# Main.net
KiCad netlist of a schematic drawn in Altium Designer
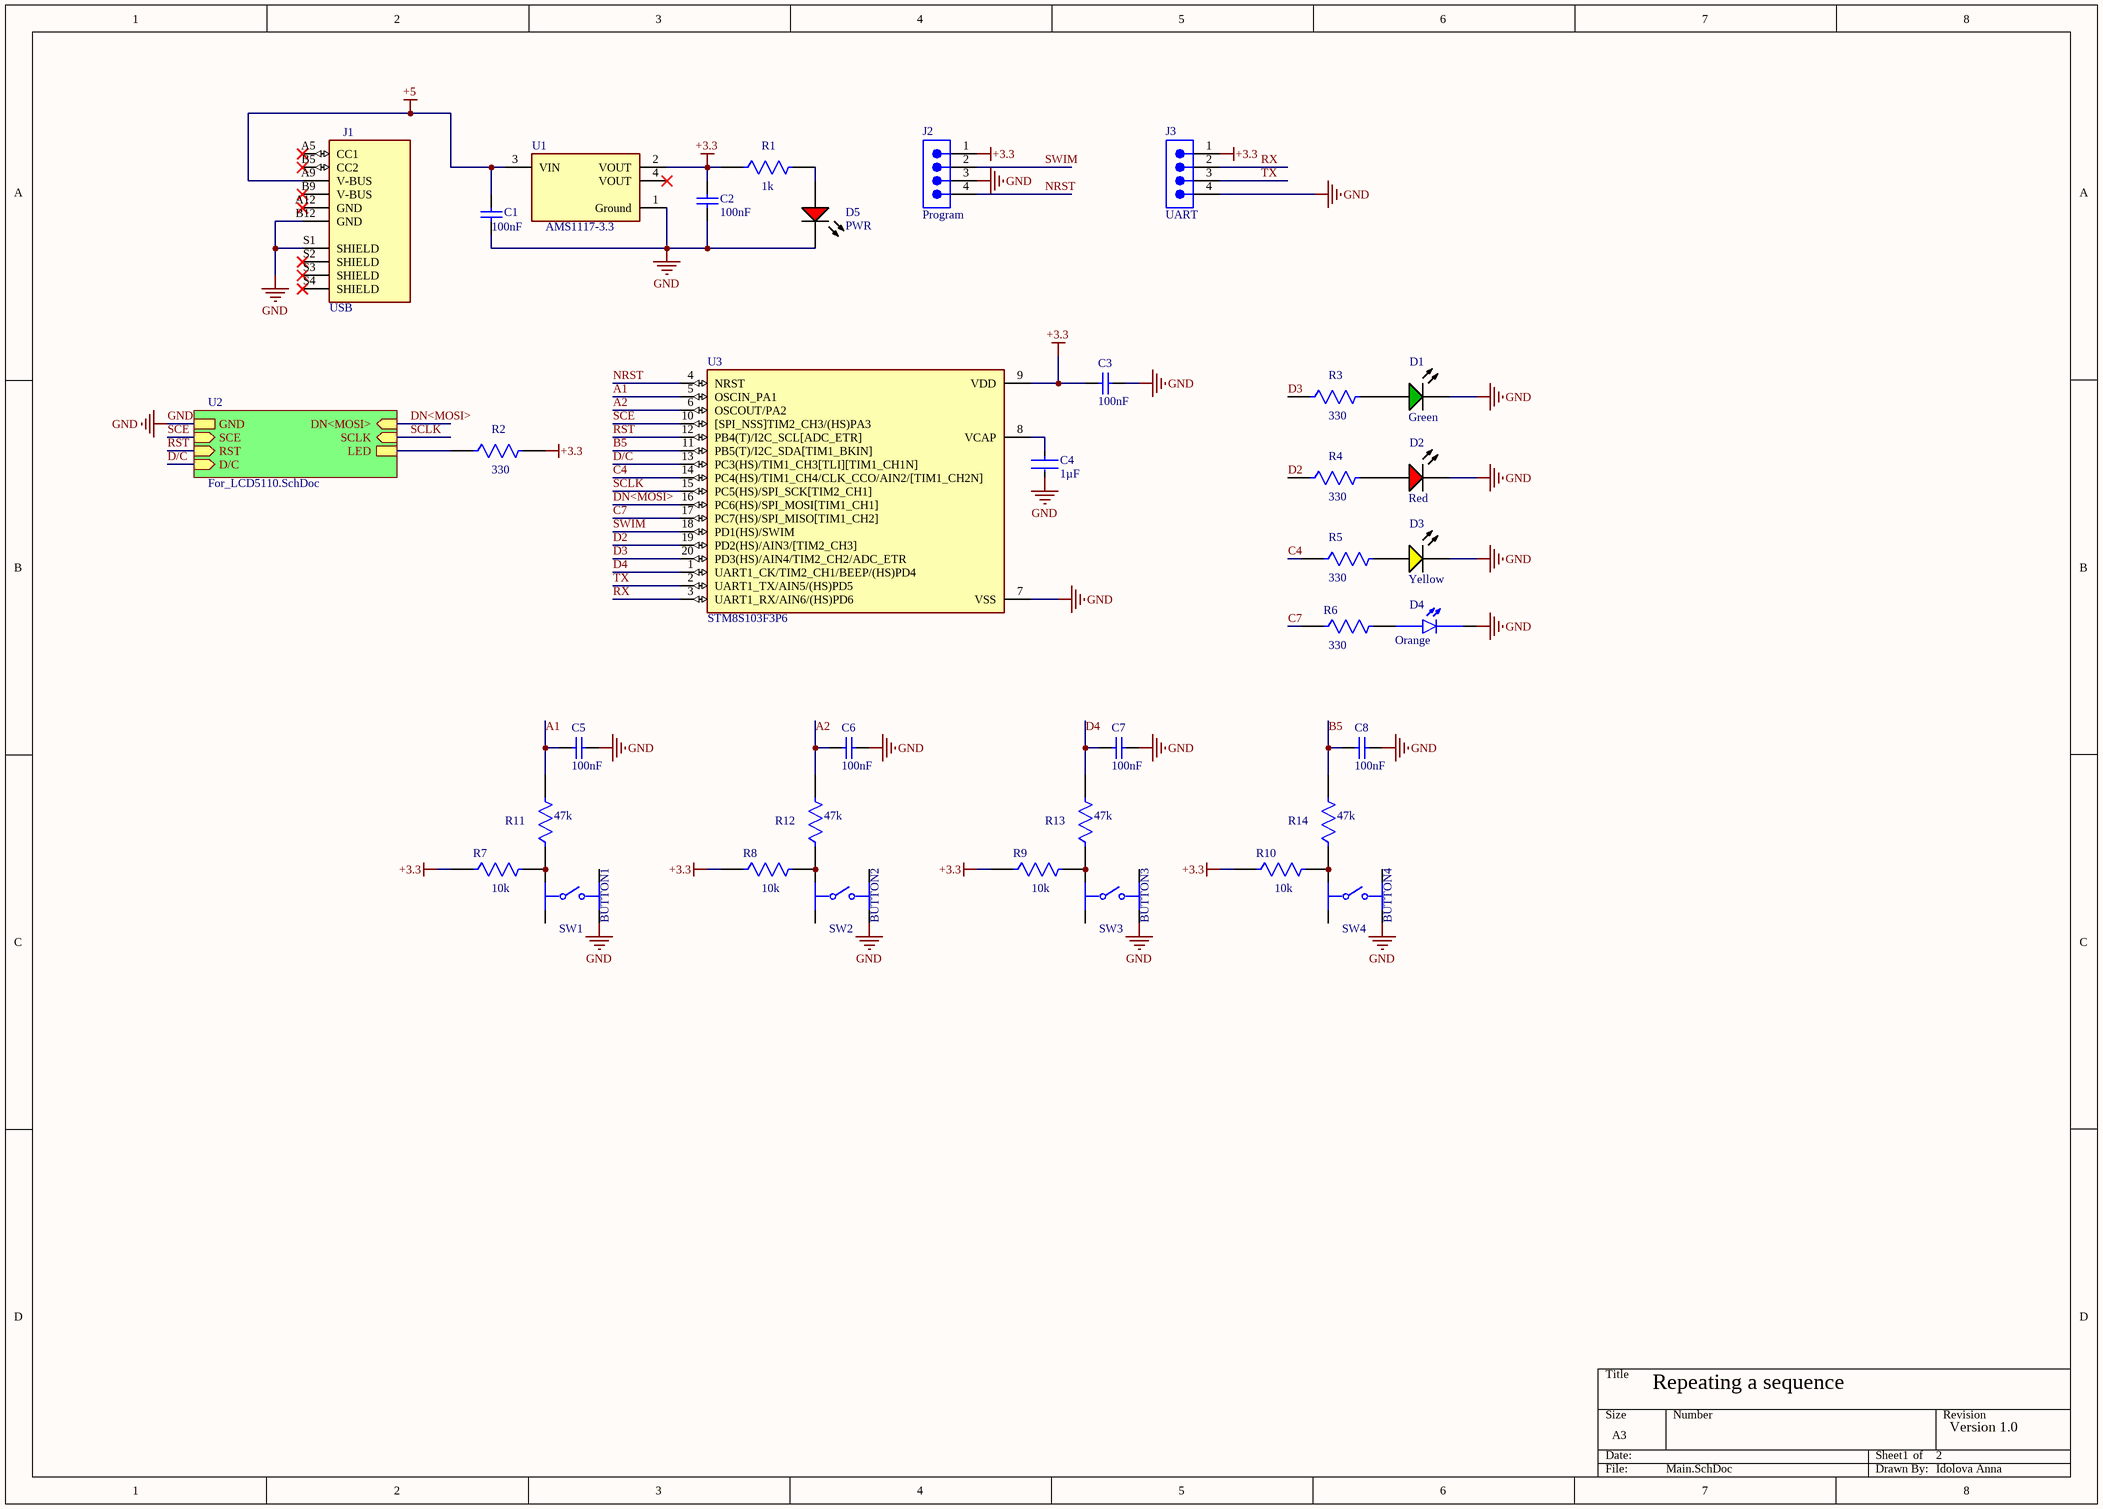
[diagram p0: Main.SchDoc]

(export (version "E")
  (design (tool "Eeschema 10.0.6"))
  (components
    (comp (ref "C1")
      (value "100nF")
      (footprint "CAPC1206(3216)100_N")
      (fields (field (name "Comment") "CAPACITOR_1206ZC104JAT2A"))
      (libsource (lib "National Technical University of Ukraine Igor Sikorsky Kyiv Polytechnic Institute- Educator Program") (part "CAP"))
    )
    (comp (ref "C2")
      (value "100nF")
      (footprint "CAPC1206(3216)100_N")
      (fields (field (name "Comment") "CAPACITOR_1206ZC104JAT2A"))
      (libsource (lib "National Technical University of Ukraine Igor Sikorsky Kyiv Polytechnic Institute- Educator Program") (part "CAP"))
    )
    (comp (ref "C3")
      (value "100nF")
      (footprint "CAPC1206(3216)100_N")
      (fields (field (name "Comment") "CAPACITOR_1206ZC104JAT2A"))
      (libsource (lib "National Technical University of Ukraine Igor Sikorsky Kyiv Polytechnic Institute- Educator Program") (part "CAP"))
    )
    (comp (ref "C4")
      (value "1µF")
      (footprint "FP-CL21-IPC_B")
      (fields (field (name "Comment") "CL21F105ZAFNNNF"))
      (libsource (lib "National Technical University of Ukraine Igor Sikorsky Kyiv Polytechnic Institute- Educator Program") (part "b4654b650e69147ec39a6b967a45e02"))
    )
    (comp (ref "C5")
      (value "100nF")
      (footprint "CAPC1206(3216)100_N")
      (fields (field (name "Comment") "CAPACITOR_1206ZC104JAT2A"))
      (libsource (lib "National Technical University of Ukraine Igor Sikorsky Kyiv Polytechnic Institute- Educator Program") (part "CAP"))
    )
    (comp (ref "C6")
      (value "100nF")
      (footprint "CAPC1206(3216)100_N")
      (fields (field (name "Comment") "CAPACITOR_1206ZC104JAT2A"))
      (libsource (lib "National Technical University of Ukraine Igor Sikorsky Kyiv Polytechnic Institute- Educator Program") (part "CAP"))
    )
    (comp (ref "C7")
      (value "100nF")
      (footprint "CAPC1206(3216)100_N")
      (fields (field (name "Comment") "CAPACITOR_1206ZC104JAT2A"))
      (libsource (lib "National Technical University of Ukraine Igor Sikorsky Kyiv Polytechnic Institute- Educator Program") (part "CAP"))
    )
    (comp (ref "C8")
      (value "100nF")
      (footprint "CAPC1206(3216)100_N")
      (fields (field (name "Comment") "CAPACITOR_1206ZC104JAT2A"))
      (libsource (lib "National Technical University of Ukraine Igor Sikorsky Kyiv Polytechnic Institute- Educator Program") (part "CAP"))
    )
    (comp (ref "D1")
      (value "Green")
      (footprint "KING-WP7113SGD_V")
      (description "LED Green, 62.5 mW, 25 mA, -40 to 85 degC, 2-Pin THD, RoHS, Bulk")
      (fields (field (name "MANUFACTURER") "Kingbright") (field (name "POWER") "62.5mW"))
      (libsource (lib "National Technical University of Ukraine Igor Sikorsky Kyiv Polytechnic Institute- Educator Program") (part "LED-GREEN-AK-2"))
    )
    (comp (ref "D2")
      (value "Red")
      (footprint "KING-WP7113SRDD_V")
      (description "The Super Bright Red Source Color Device, 1.85 V, -40 to 85 degC, 2-Pin THD, RoHS, Tape and Reel")
      (fields (field (name "MANUFACTURER") "Kingbright"))
      (libsource (lib "National Technical University of Ukraine Igor Sikorsky Kyiv Polytechnic Institute- Educator Program") (part "LED-RED-AK-2"))
    )
    (comp (ref "D3")
      (value "Yellow")
      (footprint "KING-WP7113SYD_V")
      (description "The Super Bright Yellow Source Color Device, 2 V, -40 to 85 degC, 2-Pin THD, RoHS, Tape and Reel")
      (fields (field (name "MANUFACTURER") "Kingbright"))
      (libsource (lib "National Technical University of Ukraine Igor Sikorsky Kyiv Polytechnic Institute- Educator Program") (part "LED-YELLOW-AK-2"))
    )
    (comp (ref "D4")
      (value "Orange")
      (footprint "LED_WP7113SEC")
      (description "LED Thru-Hole Orange T1-3/4 5mm Clear Lens 30mA 610nm 2500mcd Round")
      (fields (field (name "MP") "WP7113SEC") (field (name "MF") "Kingbright"))
      (libsource (lib "National Technical University of Ukraine Igor Sikorsky Kyiv Polytechnic Institute- Educator Program") (part "WP7113SEC"))
    )
    (comp (ref "D5")
      (value "PWR")
      (footprint "KING-WP7113SRDD_V")
      (description "The Super Bright Red Source Color Device, 1.85 V, -40 to 85 degC, 2-Pin THD, RoHS, Tape and Reel")
      (fields (field (name "MANUFACTURER") "Kingbright"))
      (libsource (lib "National Technical University of Ukraine Igor Sikorsky Kyiv Polytechnic Institute- Educator Program") (part "LED-RED-AK-2"))
    )
    (comp (ref "J1")
      (value "USB")
      (footprint "CUI_UJC-HP-3-SMT-TR")
      (fields (field (name "MP") "UJC-HP-3-SMT-TR"))
      (libsource (lib "National Technical University of Ukraine Igor Sikorsky Kyiv Polytechnic Institute- Educator Program") (part "UJC-HP-3-SMT-TR"))
    )
    (comp (ref "J2")
      (value "Program")
      (footprint "61300411021")
      (libsource (lib "National Technical University of Ukraine Igor Sikorsky Kyiv Polytechnic Institute- Educator Program") (part "CMP-1502-01063-3"))
    )
    (comp (ref "J3")
      (value "UART")
      (footprint "61300411021")
      (libsource (lib "National Technical University of Ukraine Igor Sikorsky Kyiv Polytechnic Institute- Educator Program") (part "CMP-1502-01063-3"))
    )
    (comp (ref "R1")
      (value "1k")
      (footprint "FP-RC1005-IPC_C")
      (fields
        (field (name "POWER") "60mW")
        (field (name "TOLERANCE") "1%")
        (field (name "Comment") "RESISTOR__RC1005F102CS")
      )
      (libsource (lib "National Technical University of Ukraine Igor Sikorsky Kyiv Polytechnic Institute- Educator Program") (part "1029c3af85768c4190bb7ad29bc67b5"))
    )
    (comp (ref "R2")
      (value "330")
      (footprint "FP-MCR18-IPC_B")
      (fields
        (field (name "TOLERANCE") "1%")
        (field (name "POWER") "250mW")
        (field (name "Comment") "MCR18EZPF3300")
      )
      (libsource (lib "National Technical University of Ukraine Igor Sikorsky Kyiv Polytechnic Institute- Educator Program") (part "1029c3af85768c4190bb7ad29bc67b5"))
    )
    (comp (ref "R3")
      (value "330")
      (footprint "FP-MCR18-IPC_B")
      (fields
        (field (name "TOLERANCE") "1%")
        (field (name "POWER") "250mW")
        (field (name "Comment") "MCR18EZPF3300")
      )
      (libsource (lib "National Technical University of Ukraine Igor Sikorsky Kyiv Polytechnic Institute- Educator Program") (part "1029c3af85768c4190bb7ad29bc67b5"))
    )
    (comp (ref "R4")
      (value "330")
      (footprint "FP-MCR18-IPC_B")
      (fields
        (field (name "TOLERANCE") "1%")
        (field (name "POWER") "250mW")
        (field (name "Comment") "MCR18EZPF3300")
      )
      (libsource (lib "National Technical University of Ukraine Igor Sikorsky Kyiv Polytechnic Institute- Educator Program") (part "1029c3af85768c4190bb7ad29bc67b5"))
    )
    (comp (ref "R5")
      (value "330")
      (footprint "FP-MCR18-IPC_B")
      (fields
        (field (name "TOLERANCE") "1%")
        (field (name "POWER") "250mW")
        (field (name "Comment") "MCR18EZPF3300")
      )
      (libsource (lib "National Technical University of Ukraine Igor Sikorsky Kyiv Polytechnic Institute- Educator Program") (part "1029c3af85768c4190bb7ad29bc67b5"))
    )
    (comp (ref "R6")
      (value "330")
      (footprint "FP-MCR18-IPC_B")
      (fields
        (field (name "TOLERANCE") "1%")
        (field (name "POWER") "250mW")
        (field (name "Comment") "MCR18EZPF3300")
      )
      (libsource (lib "National Technical University of Ukraine Igor Sikorsky Kyiv Polytechnic Institute- Educator Program") (part "1029c3af85768c4190bb7ad29bc67b5"))
    )
    (comp (ref "R7")
      (value "10k")
      (footprint "FP-TFCR0402-IPC_A")
      (description "Fixed Resistor, Thin Film, 0.063W, 10000ohm, 25V, 0.1% +/-Tol, 50ppm/Cel, Surface Mount, 0402")
      (fields (field (name "TOLERANCE") "0.1%") (field (name "Comment") "TFCR0402-16W-C-1002BT"))
      (libsource (lib "National Technical University of Ukraine Igor Sikorsky Kyiv Polytechnic Institute- Educator Program") (part "1029c3af85768c4190bb7ad29bc67b5"))
    )
    (comp (ref "R8")
      (value "10k")
      (footprint "FP-TFCR0402-IPC_A")
      (description "Fixed Resistor, Thin Film, 0.063W, 10000ohm, 25V, 0.1% +/-Tol, 50ppm/Cel, Surface Mount, 0402")
      (fields (field (name "TOLERANCE") "0.1%") (field (name "Comment") "TFCR0402-16W-C-1002BT"))
      (libsource (lib "National Technical University of Ukraine Igor Sikorsky Kyiv Polytechnic Institute- Educator Program") (part "1029c3af85768c4190bb7ad29bc67b5"))
    )
    (comp (ref "R9")
      (value "10k")
      (footprint "FP-TFCR0402-IPC_A")
      (description "Fixed Resistor, Thin Film, 0.063W, 10000ohm, 25V, 0.1% +/-Tol, 50ppm/Cel, Surface Mount, 0402")
      (fields (field (name "TOLERANCE") "0.1%") (field (name "Comment") "TFCR0402-16W-C-1002BT"))
      (libsource (lib "National Technical University of Ukraine Igor Sikorsky Kyiv Polytechnic Institute- Educator Program") (part "1029c3af85768c4190bb7ad29bc67b5"))
    )
    (comp (ref "R10")
      (value "10k")
      (footprint "FP-TFCR0402-IPC_A")
      (description "Fixed Resistor, Thin Film, 0.063W, 10000ohm, 25V, 0.1% +/-Tol, 50ppm/Cel, Surface Mount, 0402")
      (fields (field (name "TOLERANCE") "0.1%") (field (name "Comment") "TFCR0402-16W-C-1002BT"))
      (libsource (lib "National Technical University of Ukraine Igor Sikorsky Kyiv Polytechnic Institute- Educator Program") (part "1029c3af85768c4190bb7ad29bc67b5"))
    )
    (comp (ref "R11")
      (value "47k")
      (footprint "FP-RC1005-IPC_C")
      (description "Res Thin Film 0603 47K Ohm 0.1% 0.063W(1/16W) ±25ppm/C Pad SMD T/R Medical")
      (fields (field (name "TOLERANCE") "0.1%") (field (name "Comment") "RESISTOR__RC1005F102CS"))
      (libsource (lib "") (part "1029c3af85768c4190bb7ad29bc67b5_1"))
    )
    (comp (ref "R12")
      (value "47k")
      (footprint "FP-RC1005-IPC_C")
      (description "Res Thin Film 0603 47K Ohm 0.1% 0.063W(1/16W) ±25ppm/C Pad SMD T/R Medical")
      (fields (field (name "TOLERANCE") "0.1%") (field (name "Comment") "RESISTOR__RC1005F102CS"))
      (libsource (lib "") (part "1029c3af85768c4190bb7ad29bc67b5_1"))
    )
    (comp (ref "R13")
      (value "47k")
      (footprint "FP-RC1005-IPC_C")
      (description "Res Thin Film 0603 47K Ohm 0.1% 0.063W(1/16W) ±25ppm/C Pad SMD T/R Medical")
      (fields (field (name "TOLERANCE") "0.1%") (field (name "Comment") "RESISTOR__RC1005F102CS"))
      (libsource (lib "") (part "1029c3af85768c4190bb7ad29bc67b5_1"))
    )
    (comp (ref "R14")
      (value "47k")
      (footprint "FP-RC1005-IPC_C")
      (description "Res Thin Film 0603 47K Ohm 0.1% 0.063W(1/16W) ±25ppm/C Pad SMD T/R Medical")
      (fields (field (name "TOLERANCE") "0.1%") (field (name "Comment") "RESISTOR__RC1005F102CS"))
      (libsource (lib "") (part "1029c3af85768c4190bb7ad29bc67b5_1"))
    )
    (comp (ref "SW1")
      (value "BUTTON1")
      (footprint "FP-PTS645SM43SMTR92LFS-MFG")
      (libsource (lib "National Technical University of Ukraine Igor Sikorsky Kyiv Polytechnic Institute- Educator Program") (part "1adf0dd01260c80cf25a44bfd6b99ba"))
    )
    (comp (ref "SW2")
      (value "BUTTON2")
      (footprint "FP-PTS645SM43SMTR92LFS-MFG")
      (libsource (lib "National Technical University of Ukraine Igor Sikorsky Kyiv Polytechnic Institute- Educator Program") (part "1adf0dd01260c80cf25a44bfd6b99ba"))
    )
    (comp (ref "SW3")
      (value "BUTTON3")
      (footprint "FP-PTS645SM43SMTR92LFS-MFG")
      (libsource (lib "National Technical University of Ukraine Igor Sikorsky Kyiv Polytechnic Institute- Educator Program") (part "1adf0dd01260c80cf25a44bfd6b99ba"))
    )
    (comp (ref "SW4")
      (value "BUTTON4")
      (footprint "FP-PTS645SM43SMTR92LFS-MFG")
      (libsource (lib "National Technical University of Ukraine Igor Sikorsky Kyiv Polytechnic Institute- Educator Program") (part "1adf0dd01260c80cf25a44bfd6b99ba"))
    )
    (comp (ref "U1")
      (value "AMS1117-3.3")
      (footprint "FP-AMS1117-IPC_B")
      (description "Fixed Positive LDO Regulator, 3.3V, 1.3V Dropout, PDSO3")
      (libsource (lib "National Technical University of Ukraine Igor Sikorsky Kyiv Polytechnic Institute- Educator Program") (part "8bdbb5f8e77002000e30dd2845d0354"))
    )
    (comp (ref "U3")
      (value "STM8S103F3P6")
      (footprint "SOP65P640X120-20N")
      (description "STM8 series Microcontroller IC 8-Bit 16MHz 8KB (8K x 8) FLASH 20-TSSOP")
      (fields (field (name "MF") "STMicroelectronics"))
      (libsource (lib "National Technical University of Ukraine Igor Sikorsky Kyiv Polytechnic Institute- Educator Program") (part "STM8S103F3P6"))
    )
  )
  (nets
    (net (code "1") (name "+3.3") (class "Default")
      (node (ref "C2") (pin "2") (pinfunction "2_2") (pintype "passive"))
      (node (ref "C3") (pin "1") (pinfunction "1_1") (pintype "passive"))
      (node (ref "J2") (pin "1") (pinfunction "1_1") (pintype "passive"))
      (node (ref "J3") (pin "1") (pinfunction "1_1") (pintype "passive"))
      (node (ref "R1") (pin "1") (pinfunction "1_1") (pintype "passive"))
      (node (ref "R10") (pin "1") (pinfunction "1_1") (pintype "passive"))
      (node (ref "R2") (pin "2") (pinfunction "2_2") (pintype "passive"))
      (node (ref "R7") (pin "1") (pinfunction "1_1") (pintype "passive"))
      (node (ref "R8") (pin "1") (pinfunction "1_1") (pintype "passive"))
      (node (ref "R9") (pin "1") (pinfunction "1_1") (pintype "passive"))
      (node (ref "U1") (pin "2") (pinfunction "VOUT_2") (pintype "passive"))
      (node (ref "U3") (pin "9") (pinfunction "VDD_9") (pintype "power_in"))
    )
    (net (code "2") (name "+5") (class "Default")
      (node (ref "C1") (pin "2") (pinfunction "2_2") (pintype "passive"))
      (node (ref "J1") (pin "A9") (pinfunction "V-BUS_A9") (pintype "power_in"))
      (node (ref "U1") (pin "3") (pinfunction "VIN_3") (pintype "power_in"))
    )
    (net (code "3") (name "/A1") (class "Default")
      (node (ref "C5") (pin "1") (pinfunction "1_1") (pintype "passive"))
      (node (ref "R11") (pin "1") (pinfunction "1_1") (pintype "passive"))
      (node (ref "U3") (pin "5") (pinfunction "OSCIN_PA1_5") (pintype "bidirectional"))
    )
    (net (code "4") (name "/A2") (class "Default")
      (node (ref "C6") (pin "1") (pinfunction "1_1") (pintype "passive"))
      (node (ref "R12") (pin "1") (pinfunction "1_1") (pintype "passive"))
      (node (ref "U3") (pin "6") (pinfunction "OSCOUT/PA2_6") (pintype "bidirectional"))
    )
    (net (code "5") (name "/B5") (class "Default")
      (node (ref "C8") (pin "1") (pinfunction "1_1") (pintype "passive"))
      (node (ref "R14") (pin "1") (pinfunction "1_1") (pintype "passive"))
      (node (ref "U3") (pin "11") (pinfunction "PB5(T)/I2C_SDA[TIM1_BKIN]_11") (pintype "bidirectional"))
    )
    (net (code "6") (name "/C4") (class "Default")
      (node (ref "R5") (pin "1") (pinfunction "1_1") (pintype "passive"))
      (node (ref "U3") (pin "14") (pinfunction "PC4(HS)/TIM1_CH4/CLK_CCO/AIN2/[TIM1_CH2N]_14") (pintype "bidirectional"))
    )
    (net (code "7") (name "/C7") (class "Default")
      (node (ref "R6") (pin "1") (pinfunction "1_1") (pintype "passive"))
      (node (ref "U3") (pin "17") (pinfunction "PC7(HS)/SPI_MISO[TIM1_CH2]_17") (pintype "bidirectional"))
    )
    (net (code "8") (name "/D2") (class "Default")
      (node (ref "R4") (pin "1") (pinfunction "1_1") (pintype "passive"))
      (node (ref "U3") (pin "19") (pinfunction "PD2(HS)/AIN3/[TIM2_CH3]_19") (pintype "bidirectional"))
    )
    (net (code "9") (name "/D3") (class "Default")
      (node (ref "R3") (pin "1") (pinfunction "1_1") (pintype "passive"))
      (node (ref "U3") (pin "20") (pinfunction "PD3(HS)/AIN4/TIM2_CH2/ADC_ETR_20") (pintype "bidirectional"))
    )
    (net (code "10") (name "/D4") (class "Default")
      (node (ref "C7") (pin "1") (pinfunction "1_1") (pintype "passive"))
      (node (ref "R13") (pin "1") (pinfunction "1_1") (pintype "passive"))
      (node (ref "U3") (pin "1") (pinfunction "UART1_CK/TIM2_CH1/BEEP/(HS)PD4_1") (pintype "bidirectional"))
    )
    (net (code "11") (name "/DN<MOSI>") (class "Default")
      (node (ref "U3") (pin "16") (pinfunction "PC6(HS)/SPI_MOSI[TIM1_CH1]_16") (pintype "bidirectional"))
    )
    (net (code "12") (name "/D{slash}C") (class "Default")
      (node (ref "U3") (pin "13") (pinfunction "PC3(HS)/TIM1_CH3[TLI][TIM1_CH1N]_13") (pintype "bidirectional"))
    )
    (net (code "13") (name "/LED") (class "Default")
      (node (ref "R2") (pin "1") (pinfunction "1_1") (pintype "passive"))
    )
    (net (code "14") (name "/NRST") (class "Default")
      (node (ref "J2") (pin "4") (pinfunction "4_4") (pintype "passive"))
      (node (ref "U3") (pin "4") (pinfunction "NRST_4") (pintype "bidirectional"))
    )
    (net (code "15") (name "/RST") (class "Default")
      (node (ref "U3") (pin "12") (pinfunction "PB4(T)/I2C_SCL[ADC_ETR]_12") (pintype "bidirectional"))
    )
    (net (code "16") (name "/RX") (class "Default")
      (node (ref "J3") (pin "2") (pinfunction "2_2") (pintype "passive"))
      (node (ref "U3") (pin "3") (pinfunction "UART1_RX/AIN6/(HS)PD6_3") (pintype "bidirectional"))
    )
    (net (code "17") (name "/SCE") (class "Default")
      (node (ref "U3") (pin "10") (pinfunction "[SPI_NSS]TIM2_CH3/(HS)PA3_10") (pintype "bidirectional"))
    )
    (net (code "18") (name "/SCLK") (class "Default")
      (node (ref "U3") (pin "15") (pinfunction "PC5(HS)/SPI_SCK[TIM2_CH1]_15") (pintype "bidirectional"))
    )
    (net (code "19") (name "/SWIM") (class "Default")
      (node (ref "J2") (pin "2") (pinfunction "2_2") (pintype "passive"))
      (node (ref "U3") (pin "18") (pinfunction "PD1(HS)/SWIM_18") (pintype "bidirectional"))
    )
    (net (code "20") (name "/TX") (class "Default")
      (node (ref "J3") (pin "3") (pinfunction "3_3") (pintype "passive"))
      (node (ref "U3") (pin "2") (pinfunction "UART1_TX/AIN5/(HS)PD5_2") (pintype "bidirectional"))
    )
    (net (code "21") (name "GND") (class "Default")
      (node (ref "C1") (pin "1") (pinfunction "1_1") (pintype "passive"))
      (node (ref "C2") (pin "1") (pinfunction "1_1") (pintype "passive"))
      (node (ref "C3") (pin "2") (pinfunction "2_2") (pintype "passive"))
      (node (ref "C4") (pin "2") (pinfunction "2_2") (pintype "passive"))
      (node (ref "C5") (pin "2") (pinfunction "2_2") (pintype "passive"))
      (node (ref "C6") (pin "2") (pinfunction "2_2") (pintype "passive"))
      (node (ref "C7") (pin "2") (pinfunction "2_2") (pintype "passive"))
      (node (ref "C8") (pin "2") (pinfunction "2_2") (pintype "passive"))
      (node (ref "D1") (pin "2") (pinfunction "K_2") (pintype "passive"))
      (node (ref "D2") (pin "2") (pinfunction "K_2") (pintype "passive"))
      (node (ref "D3") (pin "2") (pinfunction "K_2") (pintype "passive"))
      (node (ref "D4") (pin "C") (pinfunction "C_C") (pintype "passive"))
      (node (ref "D5") (pin "2") (pinfunction "K_2") (pintype "passive"))
      (node (ref "J1") (pin "B12") (pinfunction "GND_B12") (pintype "power_in"))
      (node (ref "J1") (pin "S1") (pinfunction "SHIELD_S1") (pintype "passive"))
      (node (ref "J2") (pin "3") (pinfunction "3_3") (pintype "passive"))
      (node (ref "J3") (pin "4") (pinfunction "4_4") (pintype "passive"))
      (node (ref "SW1") (pin "2") (pinfunction "2_2") (pintype "passive"))
      (node (ref "SW2") (pin "2") (pinfunction "2_2") (pintype "passive"))
      (node (ref "SW3") (pin "2") (pinfunction "2_2") (pintype "passive"))
      (node (ref "SW4") (pin "2") (pinfunction "2_2") (pintype "passive"))
      (node (ref "U1") (pin "1") (pinfunction "Ground_1") (pintype "power_in"))
      (node (ref "U3") (pin "7") (pinfunction "VSS_7") (pintype "power_in"))
    )
    (net (code "22") (name "Net-(D1-A)") (class "Default")
      (node (ref "D1") (pin "1") (pinfunction "A_1") (pintype "passive"))
      (node (ref "R3") (pin "2") (pinfunction "2_2") (pintype "passive"))
    )
    (net (code "23") (name "Net-(D2-A)") (class "Default")
      (node (ref "D2") (pin "1") (pinfunction "A_1") (pintype "passive"))
      (node (ref "R4") (pin "2") (pinfunction "2_2") (pintype "passive"))
    )
    (net (code "24") (name "Net-(D5-A)") (class "Default")
      (node (ref "D5") (pin "1") (pinfunction "A_1") (pintype "passive"))
      (node (ref "R1") (pin "2") (pinfunction "2_2") (pintype "passive"))
    )
    (net (code "25") (name "Net-(R10-Pad2)") (class "Default")
      (node (ref "R10") (pin "2") (pinfunction "2_2") (pintype "passive"))
      (node (ref "R14") (pin "2") (pinfunction "2_2") (pintype "passive"))
      (node (ref "SW4") (pin "3") (pinfunction "3_3") (pintype "passive"))
    )
    (net (code "26") (name "Net-(R11-Pad2)") (class "Default")
      (node (ref "R11") (pin "2") (pinfunction "2_2") (pintype "passive"))
      (node (ref "R7") (pin "2") (pinfunction "2_2") (pintype "passive"))
      (node (ref "SW1") (pin "3") (pinfunction "3_3") (pintype "passive"))
    )
    (net (code "27") (name "Net-(R12-Pad2)") (class "Default")
      (node (ref "R12") (pin "2") (pinfunction "2_2") (pintype "passive"))
      (node (ref "R8") (pin "2") (pinfunction "2_2") (pintype "passive"))
      (node (ref "SW2") (pin "3") (pinfunction "3_3") (pintype "passive"))
    )
    (net (code "28") (name "Net-(R13-Pad2)") (class "Default")
      (node (ref "R13") (pin "2") (pinfunction "2_2") (pintype "passive"))
      (node (ref "R9") (pin "2") (pinfunction "2_2") (pintype "passive"))
      (node (ref "SW3") (pin "3") (pinfunction "3_3") (pintype "passive"))
    )
    (net (code "29") (name "Net-(U3-VCAP)") (class "Default")
      (node (ref "C4") (pin "1") (pinfunction "1_1") (pintype "passive"))
      (node (ref "U3") (pin "8") (pinfunction "VCAP_8") (pintype "passive"))
    )
    (net (code "30") (name "unconnected-(D3-A-Pad1)") (class "Default")
      (node (ref "D3") (pin "1") (pinfunction "A_1") (pintype "passive"))
    )
    (net (code "31") (name "unconnected-(D4-PadA)") (class "Default")
      (node (ref "D4") (pin "A") (pinfunction "A_A") (pintype "passive"))
    )
    (net (code "32") (name "unconnected-(J1-CC1-PadA5)") (class "Default")
      (node (ref "J1") (pin "A5") (pinfunction "CC1_A5") (pintype "bidirectional+no_connect"))
    )
    (net (code "33") (name "unconnected-(J1-CC2-PadB5)") (class "Default")
      (node (ref "J1") (pin "B5") (pinfunction "CC2_B5") (pintype "bidirectional+no_connect"))
    )
    (net (code "34") (name "unconnected-(J1-GND-PadA12)") (class "Default")
      (node (ref "J1") (pin "A12") (pinfunction "GND_A12") (pintype "power_in+no_connect"))
    )
    (net (code "35") (name "unconnected-(J1-SHIELD-PadS2)") (class "Default")
      (node (ref "J1") (pin "S2") (pinfunction "SHIELD_S2") (pintype "passive+no_connect"))
    )
    (net (code "36") (name "unconnected-(J1-SHIELD-PadS3)") (class "Default")
      (node (ref "J1") (pin "S3") (pinfunction "SHIELD_S3") (pintype "passive+no_connect"))
    )
    (net (code "37") (name "unconnected-(J1-SHIELD-PadS4)") (class "Default")
      (node (ref "J1") (pin "S4") (pinfunction "SHIELD_S4") (pintype "passive+no_connect"))
    )
    (net (code "38") (name "unconnected-(J1-V-BUS-PadB9)") (class "Default")
      (node (ref "J1") (pin "B9") (pinfunction "V-BUS_B9") (pintype "power_in+no_connect"))
    )
    (net (code "39") (name "unconnected-(R5-Pad2)") (class "Default")
      (node (ref "R5") (pin "2") (pinfunction "2_2") (pintype "passive"))
    )
    (net (code "40") (name "unconnected-(R6-Pad2)") (class "Default")
      (node (ref "R6") (pin "2") (pinfunction "2_2") (pintype "passive"))
    )
    (net (code "41") (name "unconnected-(SW1-Pad1)") (class "Default")
      (node (ref "SW1") (pin "1") (pinfunction "1_1") (pintype "passive"))
    )
    (net (code "42") (name "unconnected-(SW1-Pad4)") (class "Default")
      (node (ref "SW1") (pin "4") (pinfunction "4_4") (pintype "passive"))
    )
    (net (code "43") (name "unconnected-(SW2-Pad1)") (class "Default")
      (node (ref "SW2") (pin "1") (pinfunction "1_1") (pintype "passive"))
    )
    (net (code "44") (name "unconnected-(SW2-Pad4)") (class "Default")
      (node (ref "SW2") (pin "4") (pinfunction "4_4") (pintype "passive"))
    )
    (net (code "45") (name "unconnected-(SW3-Pad1)") (class "Default")
      (node (ref "SW3") (pin "1") (pinfunction "1_1") (pintype "passive"))
    )
    (net (code "46") (name "unconnected-(SW3-Pad4)") (class "Default")
      (node (ref "SW3") (pin "4") (pinfunction "4_4") (pintype "passive"))
    )
    (net (code "47") (name "unconnected-(SW4-Pad1)") (class "Default")
      (node (ref "SW4") (pin "1") (pinfunction "1_1") (pintype "passive"))
    )
    (net (code "48") (name "unconnected-(SW4-Pad4)") (class "Default")
      (node (ref "SW4") (pin "4") (pinfunction "4_4") (pintype "passive"))
    )
    (net (code "49") (name "unconnected-(U1-VOUT-Pad4)") (class "Default")
      (node (ref "U1") (pin "4") (pinfunction "VOUT_4") (pintype "passive+no_connect"))
    )
  )
)
